# USB-RIAA.net
KiCad netlist of a schematic drawn in Altium Designer
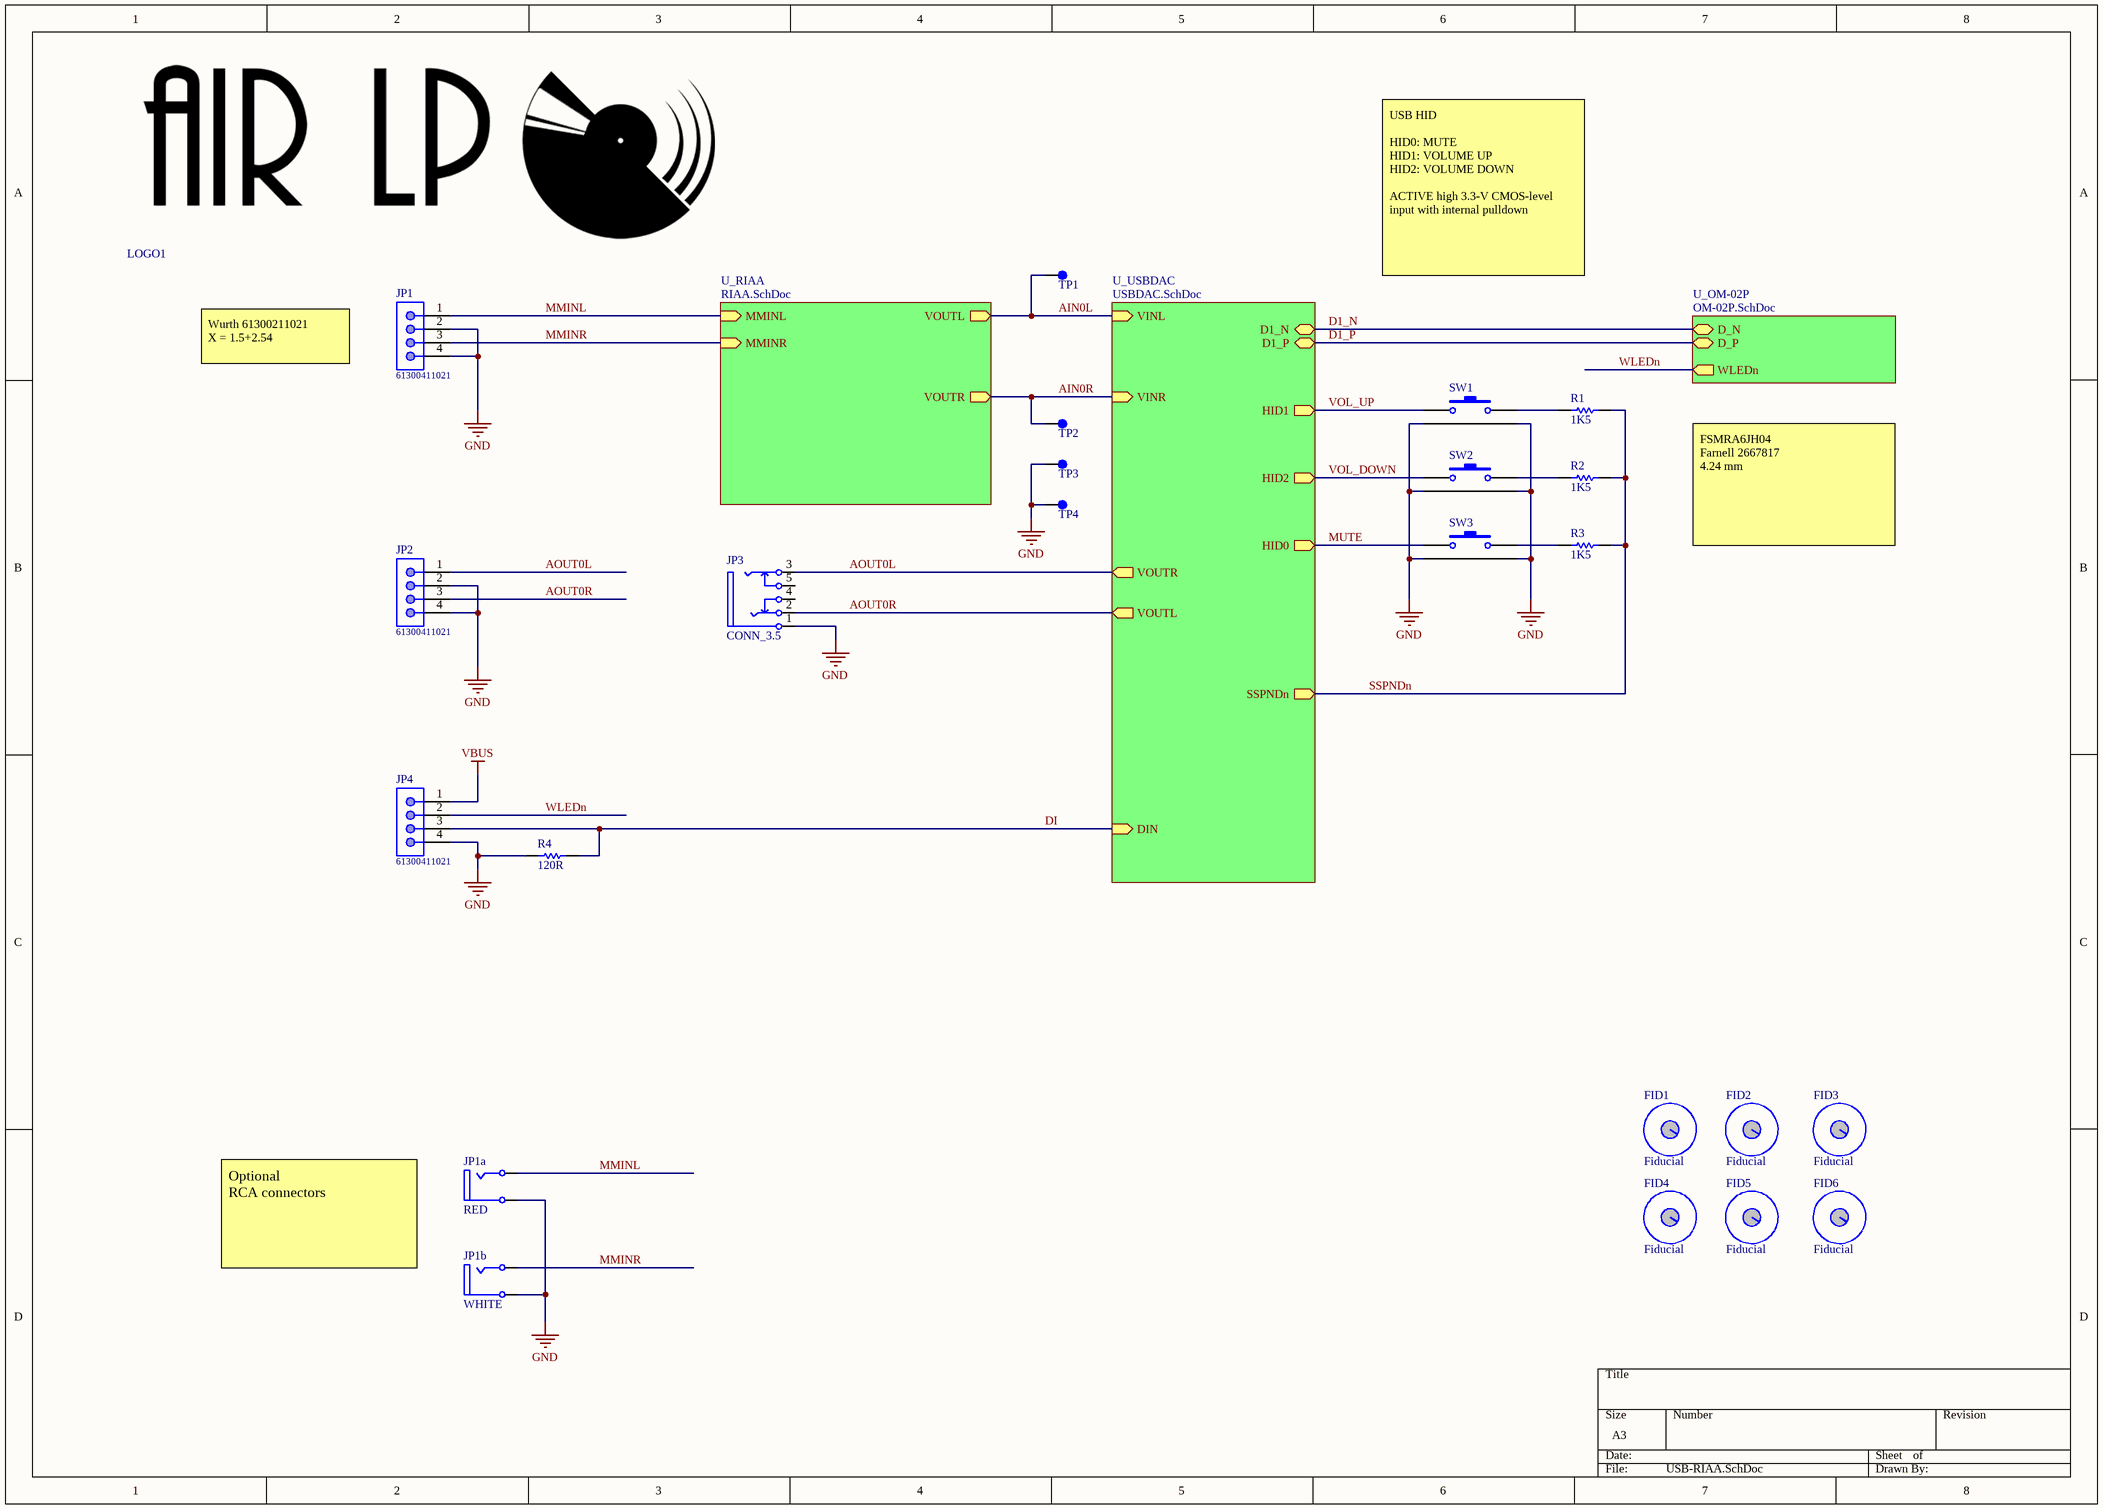
[diagram p0: USB-RIAA.SchDoc]

(export (version "E")
  (design (tool "Eeschema 10.0.6"))
  (components
    (comp (ref "FID1")
      (value "Fiducial")
      (footprint "MECH_FID_PLUS")
      (libsource (lib "micun") (part "MECH_FIDUCIAL_PLUS"))
    )
    (comp (ref "FID2")
      (value "Fiducial")
      (footprint "MECH_FID_PLUS")
      (libsource (lib "micun") (part "MECH_FIDUCIAL_PLUS"))
    )
    (comp (ref "FID3")
      (value "Fiducial")
      (footprint "MECH_FID_PLUS")
      (libsource (lib "micun") (part "MECH_FIDUCIAL_PLUS"))
    )
    (comp (ref "FID4")
      (value "Fiducial")
      (footprint "MECH_FID_PLUS")
      (libsource (lib "micun") (part "MECH_FIDUCIAL_PLUS"))
    )
    (comp (ref "FID5")
      (value "Fiducial")
      (footprint "MECH_FID_PLUS")
      (libsource (lib "micun") (part "MECH_FIDUCIAL_PLUS"))
    )
    (comp (ref "FID6")
      (value "Fiducial")
      (footprint "MECH_FID_PLUS")
      (libsource (lib "micun") (part "MECH_FIDUCIAL_PLUS"))
    )
    (comp (ref "JP1")
      (value "61300411021")
      (footprint "61300411021")
      (description "THT Angled Pin Header WR-PHD, Pitch 2.54 mm, Single Row, 4 pins")
      (fields (field (name "PUBLISHER") "Wurth Elektronik"))
      (libsource (lib "altium-import") (part "root_0_mirrored_61300411021_"))
    )
    (comp (ref "JP1a")
      (value "RED")
      (footprint "CONN_RCA-Lumberg-Red-No3D")
      (description "RCA panel-mount socket red, 1553 02 rot, Lumberg Connect GmbH")
      (fields (field (name "MPN") "1553 02 rot") (field (name "Comment") "RCA RED"))
      (libsource (lib "micun") (part "CONN_RCA_LUMBERG_RED"))
    )
    (comp (ref "JP1b")
      (value "WHITE")
      (footprint "CONN_RCA-Lumberg-White-No3D")
      (description "RCA panel-mount socket white, 1553 02 weiss, Lumberg Connect GmbH")
      (fields (field (name "MPN") "1553 02 weiss") (field (name "Comment") "RCA WHITE"))
      (libsource (lib "micun") (part "CONN_RCA_LUMBERG_WHITE"))
    )
    (comp (ref "JP2")
      (value "61300411021")
      (footprint "61300411021")
      (description "THT Angled Pin Header WR-PHD, Pitch 2.54 mm, Single Row, 4 pins")
      (fields (field (name "PUBLISHER") "Wurth Elektronik"))
      (libsource (lib "altium-import") (part "root_0_mirrored_61300411021_"))
    )
    (comp (ref "JP3")
      (value "CONN_3.5")
      (footprint "CONN-3.5_LUMBERG_1503_09")
      (description "Jack Socket, 3.5mm, Thru-Hole, Horizontal, 3-Conductor with Tip open & Ring closed")
      (fields (field (name "MPN") "1503 09"))
      (libsource (lib "micun") (part "CONN_3.5_1503_09"))
    )
    (comp (ref "JP4")
      (value "61300411021")
      (footprint "61300411021")
      (description "THT Angled Pin Header WR-PHD, Pitch 2.54 mm, Single Row, 4 pins")
      (fields (field (name "PUBLISHER") "Wurth Elektronik"))
      (libsource (lib "altium-import") (part "root_0_mirrored_61300411021_"))
    )
    (comp (ref "LOGO1")
      (value "LOGO-AIRLP")
      (footprint "LOGO-AIR-LP")
      (description "LOGO AIR LP")
      (libsource (lib "micun") (part "LOGO-AIRLP"))
    )
    (comp (ref "R1")
      (value "1K5")
      (footprint "RESC0805(2012)_N")
      (description "Generic resistor")
      (fields (field (name "Comment") "RES"))
      (libsource (lib "micun") (part "RES"))
    )
    (comp (ref "R2")
      (value "1K5")
      (footprint "RESC0805(2012)_N")
      (description "Generic resistor")
      (fields (field (name "Comment") "RES"))
      (libsource (lib "micun") (part "RES"))
    )
    (comp (ref "R3")
      (value "1K5")
      (footprint "RESC0805(2012)_N")
      (description "Generic resistor")
      (fields (field (name "Comment") "RES"))
      (libsource (lib "micun") (part "RES"))
    )
    (comp (ref "R4")
      (value "120R")
      (footprint "RESC0805(2012)_N")
      (description "120R 0.125W 5% 0805 (2012 Metric)  SMD")
      (fields (field (name "TOLERANCE") "5 %") (field (name "POWER") "0.125 W"))
      (libsource (lib "Altium Content Vault") (part "RES"))
    )
    (comp (ref "SW1")
      (value "SW_TACT_FSMRA2JH")
      (footprint "SW_FSMRA2JH")
      (description "SWITCH TACTILE SPST-NO 0.05A 12V")
      (fields (field (name "MPN") "FSMRA2JH"))
      (libsource (lib "micun") (part "SW_TACT_FSMRA2JH"))
    )
    (comp (ref "SW2")
      (value "SW_TACT_FSMRA2JH")
      (footprint "SW_FSMRA2JH")
      (description "SWITCH TACTILE SPST-NO 0.05A 12V")
      (fields (field (name "MPN") "FSMRA2JH"))
      (libsource (lib "micun") (part "SW_TACT_FSMRA2JH"))
    )
    (comp (ref "SW3")
      (value "SW_TACT_FSMRA2JH")
      (footprint "SW_FSMRA2JH")
      (description "SWITCH TACTILE SPST-NO 0.05A 12V")
      (fields (field (name "MPN") "FSMRA2JH"))
      (libsource (lib "micun") (part "SW_TACT_FSMRA2JH"))
    )
    (comp (ref "TP1")
      (value "MECH_Testpoint")
      (footprint "MECH_TP_39_mil")
      (description "Testpoint")
      (libsource (lib "micun") (part "MECH_Testpoint"))
    )
    (comp (ref "TP2")
      (value "MECH_Testpoint")
      (footprint "MECH_TP_39_mil")
      (description "Testpoint")
      (libsource (lib "micun") (part "MECH_Testpoint"))
    )
    (comp (ref "TP3")
      (value "MECH_Testpoint")
      (footprint "MECH_TP_39_mil")
      (description "Testpoint")
      (libsource (lib "micun") (part "MECH_Testpoint"))
    )
    (comp (ref "TP4")
      (value "MECH_Testpoint")
      (footprint "MECH_TP_39_mil")
      (description "Testpoint")
      (libsource (lib "micun") (part "MECH_Testpoint"))
    )
  )
  (nets
    (net (code "1") (name "/AIN0L") (class "Default")
      (node (ref "TP1") (pin "1") (pinfunction "Pin1_1") (pintype "passive"))
    )
    (net (code "2") (name "/AIN0R") (class "Default")
      (node (ref "TP2") (pin "1") (pinfunction "Pin1_1") (pintype "passive"))
    )
    (net (code "3") (name "/AOUT0L") (class "Default")
      (node (ref "JP2") (pin "1") (pinfunction "1_1") (pintype "passive"))
      (node (ref "JP3") (pin "3") (pinfunction "RN_3") (pintype "passive"))
    )
    (net (code "4") (name "/AOUT0R") (class "Default")
      (node (ref "JP2") (pin "3") (pinfunction "3_3") (pintype "passive"))
      (node (ref "JP3") (pin "2") (pinfunction "T_2") (pintype "passive"))
    )
    (net (code "7") (name "/DI") (class "Default")
      (node (ref "JP4") (pin "3") (pinfunction "3_3") (pintype "passive"))
      (node (ref "R4") (pin "2") (pinfunction "2_2") (pintype "passive"))
    )
    (net (code "8") (name "/MMINL") (class "Default")
      (node (ref "JP1") (pin "1") (pinfunction "1_1") (pintype "passive"))
      (node (ref "JP1a") (pin "4") (pinfunction "Signal_4") (pintype "passive"))
    )
    (net (code "9") (name "/MMINR") (class "Default")
      (node (ref "JP1") (pin "3") (pinfunction "3_3") (pintype "passive"))
      (node (ref "JP1b") (pin "4") (pinfunction "Signal_4") (pintype "passive"))
    )
    (net (code "10") (name "/MUTE") (class "Default")
      (node (ref "SW3") (pin "1") (pinfunction "1_1") (pintype "passive"))
    )
    (net (code "11") (name "/SSPNDn") (class "Default")
      (node (ref "R1") (pin "1") (pinfunction "1_1") (pintype "passive"))
      (node (ref "R2") (pin "1") (pinfunction "1_1") (pintype "passive"))
      (node (ref "R3") (pin "1") (pinfunction "1_1") (pintype "passive"))
    )
    (net (code "12") (name "/VOL_DOWN") (class "Default")
      (node (ref "SW2") (pin "1") (pinfunction "1_1") (pintype "passive"))
    )
    (net (code "13") (name "/VOL_UP") (class "Default")
      (node (ref "SW1") (pin "1") (pinfunction "1_1") (pintype "passive"))
    )
    (net (code "14") (name "/WLEDn") (class "Default")
      (node (ref "JP4") (pin "2") (pinfunction "2_2") (pintype "passive"))
    )
    (net (code "15") (name "GND") (class "Default")
      (node (ref "JP1") (pin "2") (pinfunction "2_2") (pintype "passive"))
      (node (ref "JP1") (pin "4") (pinfunction "4_4") (pintype "passive"))
      (node (ref "JP1a") (pin "1") (pinfunction "Ground_1") (pintype "power_in"))
      (node (ref "JP1b") (pin "1") (pinfunction "Ground_1") (pintype "power_in"))
      (node (ref "JP2") (pin "2") (pinfunction "2_2") (pintype "passive"))
      (node (ref "JP2") (pin "4") (pinfunction "4_4") (pintype "passive"))
      (node (ref "JP3") (pin "1") (pinfunction "S_1") (pintype "passive"))
      (node (ref "JP4") (pin "4") (pinfunction "4_4") (pintype "passive"))
      (node (ref "R4") (pin "1") (pinfunction "1_1") (pintype "passive"))
      (node (ref "SW1") (pin "3") (pinfunction "3_3") (pintype "passive"))
      (node (ref "SW1") (pin "4") (pinfunction "4_4") (pintype "passive"))
      (node (ref "SW2") (pin "3") (pinfunction "3_3") (pintype "passive"))
      (node (ref "SW2") (pin "4") (pinfunction "4_4") (pintype "passive"))
      (node (ref "SW3") (pin "3") (pinfunction "3_3") (pintype "passive"))
      (node (ref "SW3") (pin "4") (pinfunction "4_4") (pintype "passive"))
      (node (ref "TP3") (pin "1") (pinfunction "Pin1_1") (pintype "passive"))
      (node (ref "TP4") (pin "1") (pinfunction "Pin1_1") (pintype "passive"))
    )
    (net (code "16") (name "Net-(R1-Pad2)") (class "Default")
      (node (ref "R1") (pin "2") (pinfunction "2_2") (pintype "passive"))
      (node (ref "SW1") (pin "2") (pinfunction "2_2") (pintype "passive"))
    )
    (net (code "17") (name "Net-(R2-Pad2)") (class "Default")
      (node (ref "R2") (pin "2") (pinfunction "2_2") (pintype "passive"))
      (node (ref "SW2") (pin "2") (pinfunction "2_2") (pintype "passive"))
    )
    (net (code "18") (name "Net-(R3-Pad2)") (class "Default")
      (node (ref "R3") (pin "2") (pinfunction "2_2") (pintype "passive"))
      (node (ref "SW3") (pin "2") (pinfunction "2_2") (pintype "passive"))
    )
    (net (code "19") (name "VBUS") (class "Default")
      (node (ref "JP4") (pin "1") (pinfunction "1_1") (pintype "passive"))
    )
    (net (code "20") (name "unconnected-(JP3-Pad4)") (class "Default")
      (node (ref "JP3") (pin "4") (pinfunction "4_4") (pintype "passive"))
    )
    (net (code "21") (name "unconnected-(JP3-Pad5)") (class "Default")
      (node (ref "JP3") (pin "5") (pinfunction "5_5") (pintype "passive"))
    )
  )
)
